# ReuseBlock_1_2024-11-17.net
KiCad netlist of a schematic drawn in EasyEDA Pro
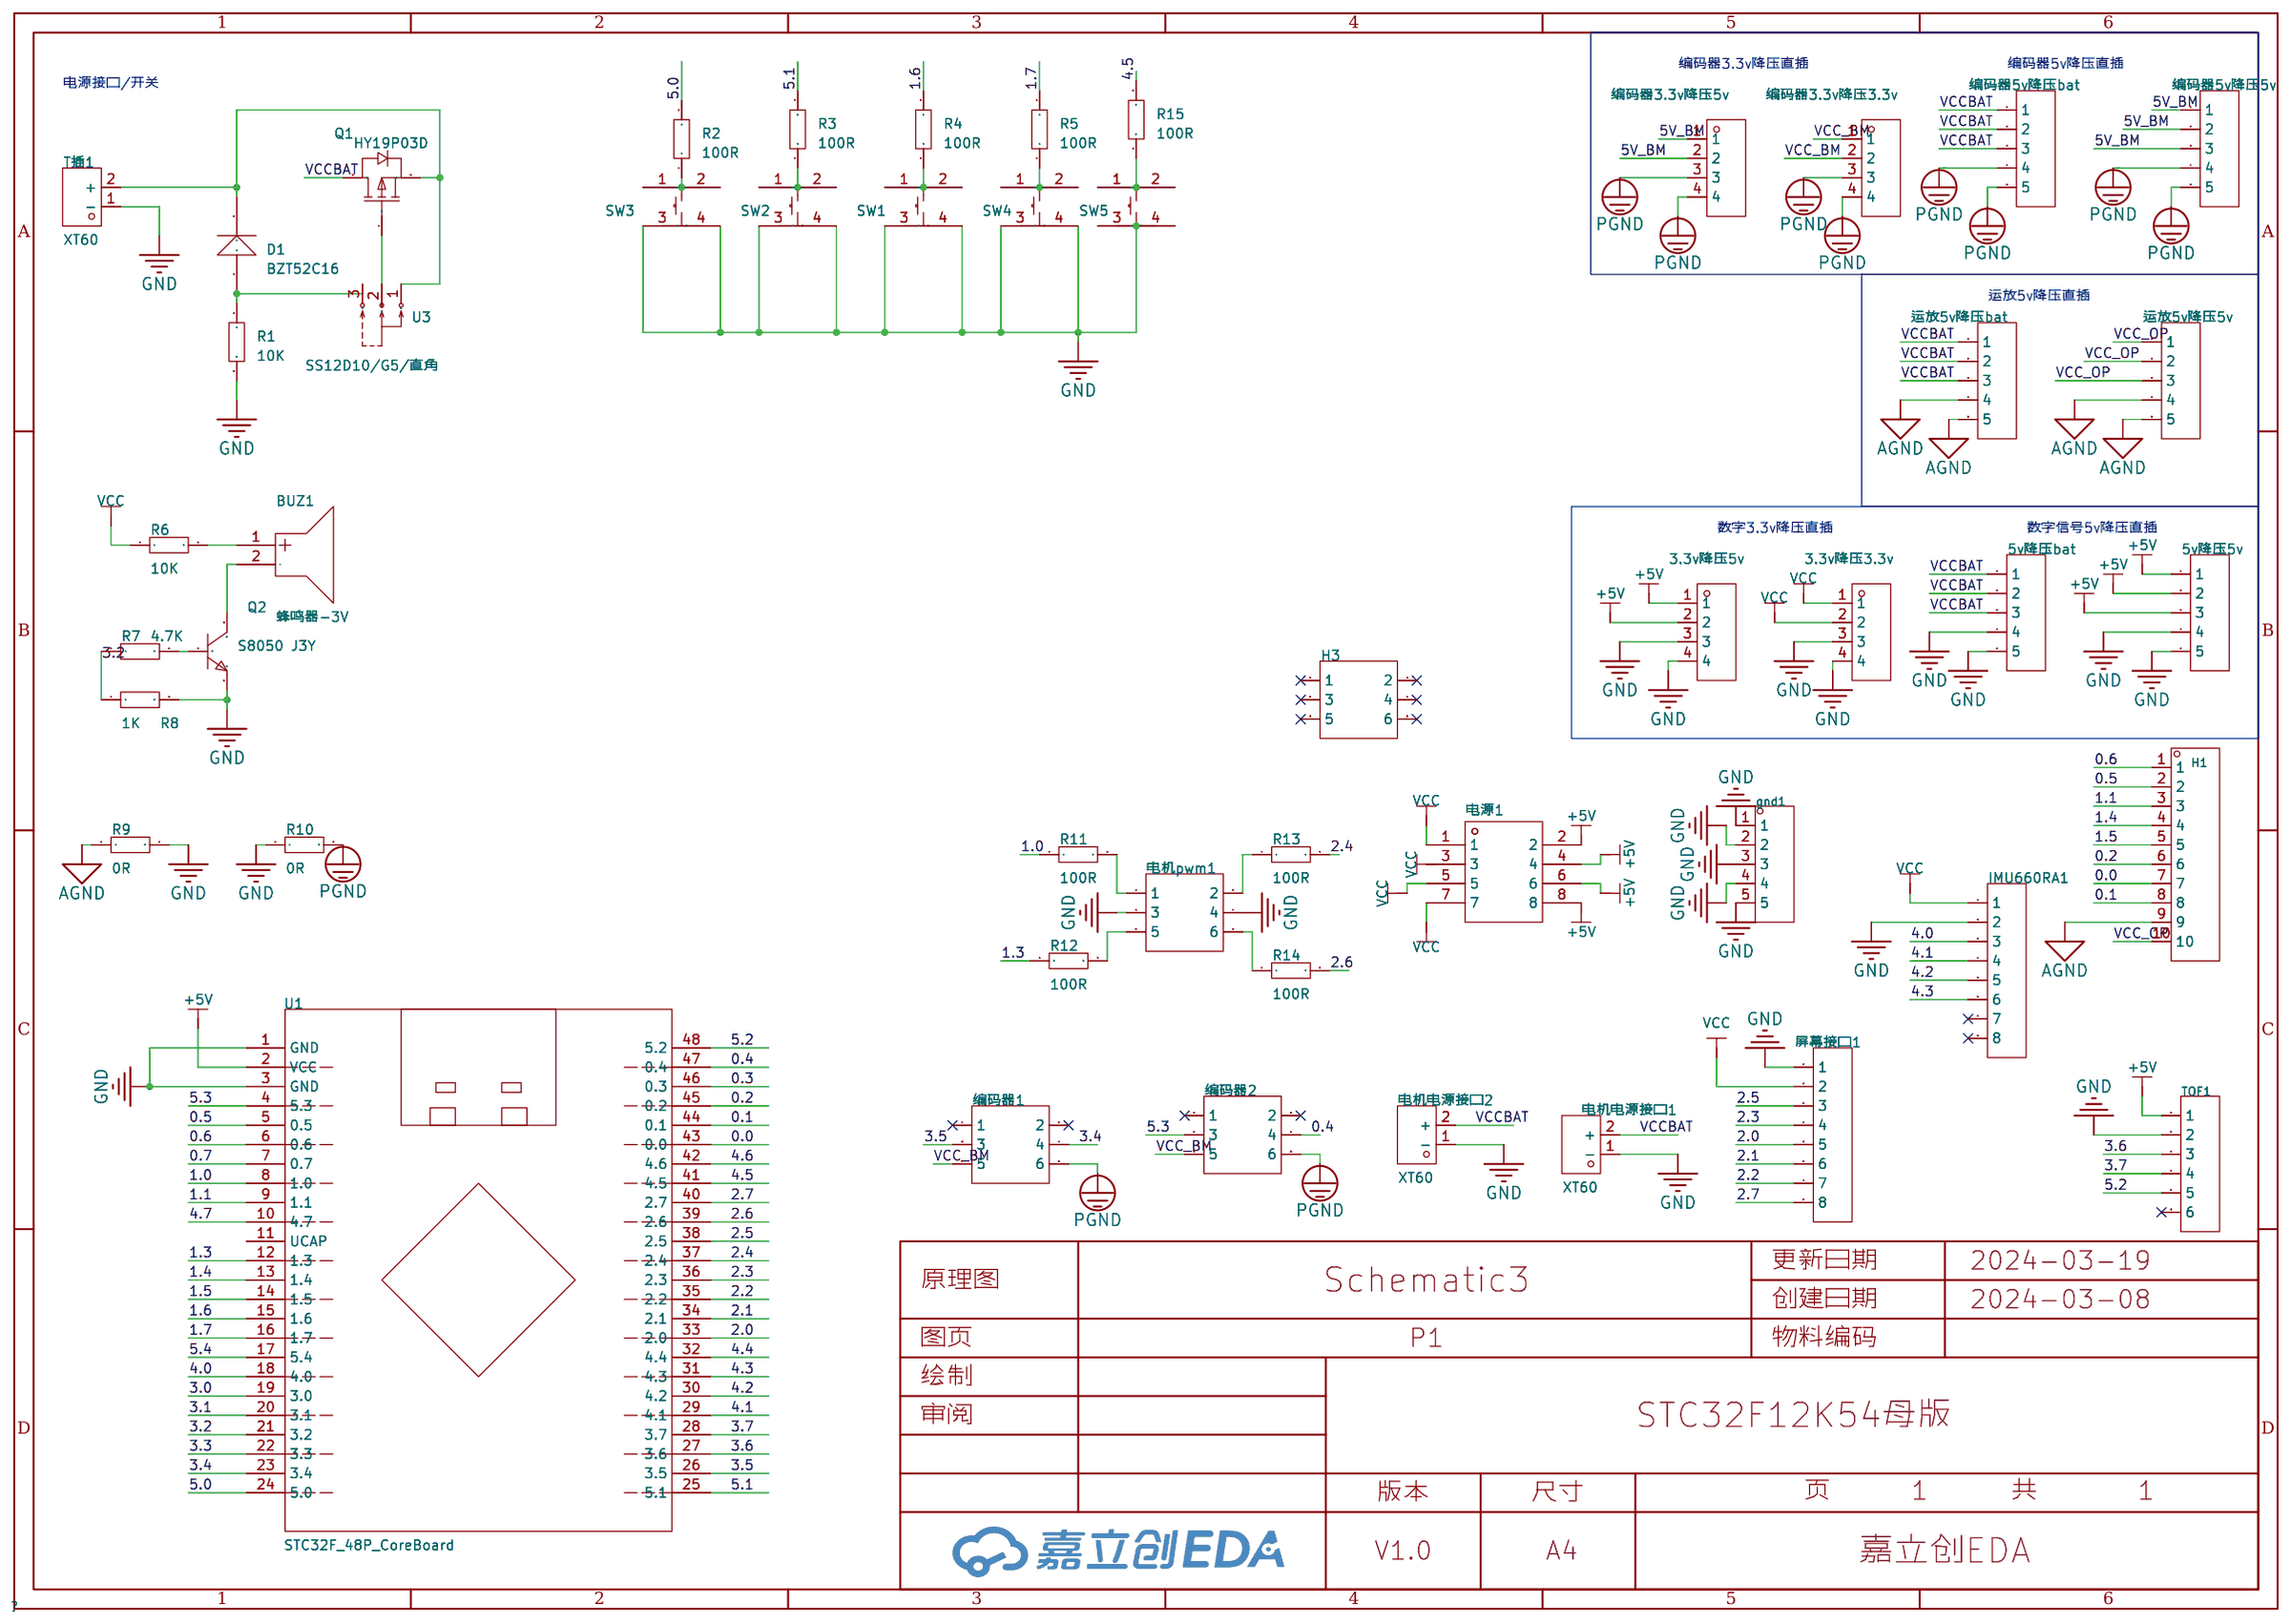
[diagram p0: schematic sheet]

(export (version "E")
  (design (tool "Eeschema 10.0.6"))
  (components
    (comp (ref "3.3v降压3.3v")
      (value "~")
      (footprint "easyedapro:HDR-TH_4P-P2.54-V-F")
      (libsource (lib "easyedapro") (part "2.54-1*4P母"))
    )
    (comp (ref "3.3v降压5v")
      (value "~")
      (footprint "easyedapro:HDR-TH_4P-P2.54-V-F")
      (libsource (lib "easyedapro") (part "2.54-1*4P母"))
    )
    (comp (ref "5v降压5v")
      (value "~")
      (footprint "easyedapro:HDR-TH_5P-P2.54-V-F")
      (libsource (lib "easyedapro") (part "Header-Female-2.54_1x5"))
    )
    (comp (ref "5v降压bat")
      (value "~")
      (footprint "easyedapro:HDR-TH_5P-P2.54-V-F")
      (libsource (lib "easyedapro") (part "Header-Female-2.54_1x5"))
    )
    (comp (ref "BUZ1")
      (value "蜂鸣器-3V")
      (footprint "easyedapro:BUZ-TH_BD12.0-P7.60-D0.6-FD")
      (libsource (lib "easyedapro") (part "蜂鸣器-3V"))
    )
    (comp (ref "D1")
      (value "BZT52C16")
      (footprint "easyedapro:SS14")
      (libsource (lib "easyedapro") (part "BZT52C16"))
    )
    (comp (ref "gnd1")
      (value "~")
      (footprint "easyedapro:HDR-TH_5P-P2.54-V-M")
      (libsource (lib "easyedapro") (part "MTP125-1105S1"))
    )
    (comp (ref "H1")
      (value "~")
      (footprint "easyedapro:HDR-TH_10P-P2.54-V-M-1")
      (libsource (lib "easyedapro") (part "Header-Male-2.54_1x10"))
    )
    (comp (ref "H3")
      (value "~")
      (footprint "easyedapro:HDR-TH_6P-P2.54-V-R2-C3-S2.54_A2541WV-2X3P")
      (libsource (lib "easyedapro") (part "HDR-M-2.54_2x3"))
    )
    (comp (ref "IMU660RA1")
      (value "~")
      (footprint "easyedapro:HDR-TH_8P-P2.54-V-F-1")
      (libsource (lib "easyedapro") (part "Header-Female-2.54_1x8"))
    )
    (comp (ref "Q1")
      (value "HY19P03D")
      (footprint "easyedapro:TO-252-3_L6.5-W5.8-P4.58-BL")
      (libsource (lib "easyedapro") (part "HY19P03D_C330375"))
    )
    (comp (ref "Q2")
      (value "S8050 J3Y")
      (footprint "easyedapro:SOT-23-3_L3.0-W1.7-P0.95-LS2.9-BR")
      (description "晶体管类型:NPN;集电极电流(Ic):500mA;集射极击穿电压(Vceo):25V;功率(Pd):300mW;直流电流增益(hFE@Ic,Vce):200@50mA,1V;")
      (fields (field (name "Manufacturer") "CJ(江苏长电/长晶)"))
      (libsource (lib "easyedapro") (part "S8050_C2146"))
    )
    (comp (ref "R1") (value "10K") (footprint "easyedapro:R0603") (libsource (lib "easyedapro") (part "电阻")))
    (comp (ref "R2") (value "100R") (footprint "easyedapro:R0603") (libsource (lib "easyedapro") (part "电阻")))
    (comp (ref "R3") (value "100R") (footprint "easyedapro:R0603") (libsource (lib "easyedapro") (part "电阻")))
    (comp (ref "R4") (value "100R") (footprint "easyedapro:R0603") (libsource (lib "easyedapro") (part "电阻")))
    (comp (ref "R5") (value "100R") (footprint "easyedapro:R0603") (libsource (lib "easyedapro") (part "电阻")))
    (comp (ref "R6") (value "10K") (footprint "easyedapro:R0603") (libsource (lib "easyedapro") (part "电阻")))
    (comp (ref "R7") (value "4.7K") (footprint "easyedapro:R0603") (libsource (lib "easyedapro") (part "电阻")))
    (comp (ref "R8") (value "1K") (footprint "easyedapro:R0603") (libsource (lib "easyedapro") (part "电阻")))
    (comp (ref "R9") (value "0R") (footprint "easyedapro:R0603") (libsource (lib "easyedapro") (part "电阻")))
    (comp (ref "R10") (value "0R") (footprint "easyedapro:R0603") (libsource (lib "easyedapro") (part "电阻")))
    (comp (ref "R11")
      (value "100R")
      (footprint "easyedapro:R0603")
      (libsource (lib "easyedapro") (part "电阻"))
    )
    (comp (ref "R12")
      (value "100R")
      (footprint "easyedapro:R0603")
      (libsource (lib "easyedapro") (part "电阻"))
    )
    (comp (ref "R13")
      (value "100R")
      (footprint "easyedapro:R0603")
      (libsource (lib "easyedapro") (part "电阻"))
    )
    (comp (ref "R14")
      (value "100R")
      (footprint "easyedapro:R0603")
      (libsource (lib "easyedapro") (part "电阻"))
    )
    (comp (ref "R15")
      (value "100R")
      (footprint "easyedapro:R0603")
      (libsource (lib "easyedapro") (part "电阻"))
    )
    (comp (ref "SW1")
      (value "TS-1095S-A2B3-C2D1")
      (footprint "easyedapro:SW-SMD_4P-L6.0-W6.0-P4.50-LS8.5")
      (description "电路结构:单刀单掷;按钮形状:圆形按钮;安装方式:-;开关长度:6mm;开关宽度:6mm;开关高度:4.5mm;带灯:-;机械寿命:-;")
      (fields (field (name "Manufacturer") "Yuandi(元迪)"))
      (libsource (lib "easyedapro") (part "TS-1095S-A2B3-C2D1"))
    )
    (comp (ref "SW2")
      (value "TS-1095S-A2B3-C2D1")
      (footprint "easyedapro:SW-SMD_4P-L6.0-W6.0-P4.50-LS8.5")
      (description "电路结构:单刀单掷;按钮形状:圆形按钮;安装方式:-;开关长度:6mm;开关宽度:6mm;开关高度:4.5mm;带灯:-;机械寿命:-;")
      (fields (field (name "Manufacturer") "Yuandi(元迪)"))
      (libsource (lib "easyedapro") (part "TS-1095S-A2B3-C2D1"))
    )
    (comp (ref "SW3")
      (value "TS-1095S-A2B3-C2D1")
      (footprint "easyedapro:SW-SMD_4P-L6.0-W6.0-P4.50-LS8.5")
      (description "电路结构:单刀单掷;按钮形状:圆形按钮;安装方式:-;开关长度:6mm;开关宽度:6mm;开关高度:4.5mm;带灯:-;机械寿命:-;")
      (fields (field (name "Manufacturer") "Yuandi(元迪)"))
      (libsource (lib "easyedapro") (part "TS-1095S-A2B3-C2D1"))
    )
    (comp (ref "SW4")
      (value "TS-1095S-A2B3-C2D1")
      (footprint "easyedapro:SW-SMD_4P-L6.0-W6.0-P4.50-LS8.5")
      (description "电路结构:单刀单掷;按钮形状:圆形按钮;安装方式:-;开关长度:6mm;开关宽度:6mm;开关高度:4.5mm;带灯:-;机械寿命:-;")
      (fields (field (name "Manufacturer") "Yuandi(元迪)"))
      (libsource (lib "easyedapro") (part "TS-1095S-A2B3-C2D1"))
    )
    (comp (ref "SW5")
      (value "TS-1095S-A2B3-C2D1")
      (footprint "easyedapro:SW-SMD_4P-L6.0-W6.0-P4.50-LS8.5")
      (description "电路结构:单刀单掷;按钮形状:圆形按钮;安装方式:-;开关长度:6mm;开关宽度:6mm;开关高度:4.5mm;带灯:-;机械寿命:-;")
      (fields (field (name "Manufacturer") "Yuandi(元迪)"))
      (libsource (lib "easyedapro") (part "TS-1095S-A2B3-C2D1"))
    )
    (comp (ref "TOF1")
      (value "~")
      (footprint "easyedapro:HDR-TH_6P-P2.54-V-M-1")
      (libsource (lib "easyedapro") (part "Header-Male-2.54_1x6"))
    )
    (comp (ref "T插1")
      (value "XT60")
      (footprint "easyedapro:CONN-TH_XT60")
      (fields (field (name "Manufacturer") "AMASS(艾迈斯)"))
      (libsource (lib "easyedapro") (part "XT60"))
    )
    (comp (ref "U1")
      (value "STC32F_48P_CoreBoard")
      (footprint "easyedapro:STC32F_48P")
      (description "逐飞科技STC32F核心板")
      (libsource (lib "easyedapro") (part "STC32F_48P_CoreBoard"))
    )
    (comp (ref "U3")
      (value "SS12D10/G5/直角")
      (footprint "easyedapro:SW-TH_SHOU-HAN_SS12D10G4")
      (libsource (lib "easyedapro") (part "SS12D10/G5/直角"))
    )
    (comp (ref "屏幕接口1")
      (value "~")
      (footprint "easyedapro:HDR-TH_8P-P2.54-V-F-1")
      (libsource (lib "easyedapro") (part "Header-Female-2.54_1x8"))
    )
    (comp (ref "电机pwm1")
      (value "~")
      (footprint "easyedapro:HDR-TH_6P-P2.54-V-R2-C3-S2.54_A2541WV-2X3P")
      (libsource (lib "easyedapro") (part "HDR-M-2.54_2x3"))
    )
    (comp (ref "电机电源接口1")
      (value "XT60")
      (footprint "easyedapro:CONN-TH_XT60")
      (fields (field (name "Manufacturer") "AMASS(艾迈斯)"))
      (libsource (lib "easyedapro") (part "XT60"))
    )
    (comp (ref "电机电源接口2")
      (value "XT60")
      (footprint "easyedapro:CONN-TH_XT60")
      (fields (field (name "Manufacturer") "AMASS(艾迈斯)"))
      (libsource (lib "easyedapro") (part "XT60"))
    )
    (comp (ref "电源1")
      (value "~")
      (footprint "easyedapro:HDR-TH_8P-P2.54-V-M-R2-C4-S2.54")
      (libsource (lib "easyedapro") (part "HDR-M-2.54_2x4"))
    )
    (comp (ref "编码器1")
      (value "~")
      (footprint "easyedapro:HDR-TH_6P-P2.54-V-R2-C3-S2.54_A2541WV-2X3P")
      (libsource (lib "easyedapro") (part "HDR-M-2.54_2x3"))
    )
    (comp (ref "编码器2")
      (value "~")
      (footprint "easyedapro:HDR-TH_6P-P2.54-V-R2-C3-S2.54_A2541WV-2X3P")
      (libsource (lib "easyedapro") (part "HDR-M-2.54_2x3"))
    )
    (comp (ref "编码器3.3v降压3.3v")
      (value "~")
      (footprint "easyedapro:HDR-TH_4P-P2.54-V-F")
      (libsource (lib "easyedapro") (part "2.54-1*4P母"))
    )
    (comp (ref "编码器3.3v降压5v")
      (value "~")
      (footprint "easyedapro:HDR-TH_4P-P2.54-V-F")
      (libsource (lib "easyedapro") (part "2.54-1*4P母"))
    )
    (comp (ref "编码器5v降压5v")
      (value "~")
      (footprint "easyedapro:HDR-TH_5P-P2.54-V-F")
      (libsource (lib "easyedapro") (part "Header-Female-2.54_1x5"))
    )
    (comp (ref "编码器5v降压bat")
      (value "~")
      (footprint "easyedapro:HDR-TH_5P-P2.54-V-F")
      (libsource (lib "easyedapro") (part "Header-Female-2.54_1x5"))
    )
    (comp (ref "运放5v降压5v")
      (value "~")
      (footprint "easyedapro:HDR-TH_5P-P2.54-V-F")
      (libsource (lib "easyedapro") (part "Header-Female-2.54_1x5"))
    )
    (comp (ref "运放5v降压bat")
      (value "~")
      (footprint "easyedapro:HDR-TH_5P-P2.54-V-F")
      (libsource (lib "easyedapro") (part "Header-Female-2.54_1x5"))
    )
  )
  (nets
    (net (code "1") (name "+5V") (class "Default")
      (node (ref "3.3v降压5v") (pin "1") (pinfunction "1_1") (pintype "unspecified"))
      (node (ref "3.3v降压5v") (pin "2") (pinfunction "2_2") (pintype "unspecified"))
      (node (ref "5v降压5v") (pin "1") (pinfunction "1_1") (pintype "input"))
      (node (ref "5v降压5v") (pin "2") (pinfunction "2_2") (pintype "input"))
      (node (ref "5v降压5v") (pin "3") (pinfunction "3_3") (pintype "input"))
      (node (ref "TOF1") (pin "1") (pinfunction "1_1") (pintype "input"))
      (node (ref "U1") (pin "2") (pinfunction "VCC_2") (pintype "unspecified"))
      (node (ref "电源1") (pin "2") (pinfunction "2_2") (pintype "input"))
      (node (ref "电源1") (pin "4") (pinfunction "4_4") (pintype "input"))
      (node (ref "电源1") (pin "6") (pinfunction "6_6") (pintype "input"))
      (node (ref "电源1") (pin "8") (pinfunction "8_8") (pintype "input"))
    )
    (net (code "2") (name "/0.0") (class "Default")
      (node (ref "H1") (pin "7") (pinfunction "7_7") (pintype "input"))
      (node (ref "U1") (pin "43") (pinfunction "0.0_43") (pintype "unspecified"))
    )
    (net (code "3") (name "/0.1") (class "Default")
      (node (ref "H1") (pin "8") (pinfunction "8_8") (pintype "input"))
      (node (ref "U1") (pin "44") (pinfunction "0.1_44") (pintype "unspecified"))
    )
    (net (code "4") (name "/0.2") (class "Default")
      (node (ref "H1") (pin "6") (pinfunction "6_6") (pintype "input"))
      (node (ref "U1") (pin "45") (pinfunction "0.2_45") (pintype "unspecified"))
    )
    (net (code "5") (name "/0.3") (class "Default")
      (node (ref "U1") (pin "46") (pinfunction "0.3_46") (pintype "unspecified"))
    )
    (net (code "6") (name "/0.4") (class "Default")
      (node (ref "U1") (pin "47") (pinfunction "0.4_47") (pintype "unspecified"))
      (node (ref "编码器2") (pin "4") (pinfunction "4_4") (pintype "input"))
    )
    (net (code "7") (name "/0.5") (class "Default")
      (node (ref "H1") (pin "2") (pinfunction "2_2") (pintype "input"))
      (node (ref "U1") (pin "5") (pinfunction "0.5_5") (pintype "unspecified"))
    )
    (net (code "8") (name "/0.6") (class "Default")
      (node (ref "H1") (pin "1") (pinfunction "1_1") (pintype "input"))
      (node (ref "U1") (pin "6") (pinfunction "0.6_6") (pintype "unspecified"))
    )
    (net (code "9") (name "/0.7") (class "Default")
      (node (ref "U1") (pin "7") (pinfunction "0.7_7") (pintype "unspecified"))
    )
    (net (code "10") (name "/1.0") (class "Default")
      (node (ref "R11") (pin "1") (pinfunction "1_1") (pintype "input"))
      (node (ref "U1") (pin "8") (pinfunction "1.0_8") (pintype "unspecified"))
    )
    (net (code "11") (name "/1.1") (class "Default")
      (node (ref "H1") (pin "3") (pinfunction "3_3") (pintype "input"))
      (node (ref "U1") (pin "9") (pinfunction "1.1_9") (pintype "unspecified"))
    )
    (net (code "12") (name "/1.3") (class "Default")
      (node (ref "R12") (pin "1") (pinfunction "1_1") (pintype "input"))
      (node (ref "U1") (pin "12") (pinfunction "1.3_12") (pintype "unspecified"))
    )
    (net (code "13") (name "/1.4") (class "Default")
      (node (ref "H1") (pin "4") (pinfunction "4_4") (pintype "input"))
      (node (ref "U1") (pin "13") (pinfunction "1.4_13") (pintype "unspecified"))
    )
    (net (code "14") (name "/1.5") (class "Default")
      (node (ref "H1") (pin "5") (pinfunction "5_5") (pintype "input"))
      (node (ref "U1") (pin "14") (pinfunction "1.5_14") (pintype "unspecified"))
    )
    (net (code "15") (name "/1.6") (class "Default")
      (node (ref "R4") (pin "2") (pinfunction "2_2") (pintype "input"))
      (node (ref "U1") (pin "15") (pinfunction "1.6_15") (pintype "unspecified"))
    )
    (net (code "16") (name "/1.7") (class "Default")
      (node (ref "R5") (pin "2") (pinfunction "2_2") (pintype "input"))
      (node (ref "U1") (pin "16") (pinfunction "1.7_16") (pintype "unspecified"))
    )
    (net (code "17") (name "/2.0") (class "Default")
      (node (ref "U1") (pin "33") (pinfunction "2.0_33") (pintype "unspecified"))
      (node (ref "屏幕接口1") (pin "5") (pinfunction "5_5") (pintype "input"))
    )
    (net (code "18") (name "/2.1") (class "Default")
      (node (ref "U1") (pin "34") (pinfunction "2.1_34") (pintype "unspecified"))
      (node (ref "屏幕接口1") (pin "6") (pinfunction "6_6") (pintype "input"))
    )
    (net (code "19") (name "/2.2") (class "Default")
      (node (ref "U1") (pin "35") (pinfunction "2.2_35") (pintype "unspecified"))
      (node (ref "屏幕接口1") (pin "7") (pinfunction "7_7") (pintype "input"))
    )
    (net (code "20") (name "/2.3") (class "Default")
      (node (ref "U1") (pin "36") (pinfunction "2.3_36") (pintype "unspecified"))
      (node (ref "屏幕接口1") (pin "4") (pinfunction "4_4") (pintype "input"))
    )
    (net (code "21") (name "/2.4") (class "Default")
      (node (ref "R13") (pin "2") (pinfunction "2_2") (pintype "input"))
      (node (ref "U1") (pin "37") (pinfunction "2.4_37") (pintype "unspecified"))
    )
    (net (code "22") (name "/2.5") (class "Default")
      (node (ref "U1") (pin "38") (pinfunction "2.5_38") (pintype "unspecified"))
      (node (ref "屏幕接口1") (pin "3") (pinfunction "3_3") (pintype "input"))
    )
    (net (code "23") (name "/2.6") (class "Default")
      (node (ref "R14") (pin "2") (pinfunction "2_2") (pintype "input"))
      (node (ref "U1") (pin "39") (pinfunction "2.6_39") (pintype "unspecified"))
    )
    (net (code "24") (name "/2.7") (class "Default")
      (node (ref "U1") (pin "40") (pinfunction "2.7_40") (pintype "unspecified"))
      (node (ref "屏幕接口1") (pin "8") (pinfunction "8_8") (pintype "input"))
    )
    (net (code "25") (name "/3.0") (class "Default")
      (node (ref "U1") (pin "19") (pinfunction "3.0_19") (pintype "unspecified"))
    )
    (net (code "26") (name "/3.1") (class "Default")
      (node (ref "U1") (pin "20") (pinfunction "3.1_20") (pintype "unspecified"))
    )
    (net (code "27") (name "/3.2") (class "Default")
      (node (ref "R7") (pin "1") (pinfunction "1_1") (pintype "input"))
      (node (ref "R8") (pin "1") (pinfunction "1_1") (pintype "input"))
      (node (ref "U1") (pin "21") (pinfunction "3.2_21") (pintype "unspecified"))
    )
    (net (code "28") (name "/3.3") (class "Default")
      (node (ref "U1") (pin "22") (pinfunction "3.3_22") (pintype "unspecified"))
    )
    (net (code "29") (name "/3.4") (class "Default")
      (node (ref "U1") (pin "23") (pinfunction "3.4_23") (pintype "unspecified"))
      (node (ref "编码器1") (pin "4") (pinfunction "4_4") (pintype "input"))
    )
    (net (code "30") (name "/3.5") (class "Default")
      (node (ref "U1") (pin "26") (pinfunction "3.5_26") (pintype "unspecified"))
      (node (ref "编码器1") (pin "3") (pinfunction "3_3") (pintype "input"))
    )
    (net (code "31") (name "/3.6") (class "Default")
      (node (ref "TOF1") (pin "3") (pinfunction "3_3") (pintype "input"))
      (node (ref "U1") (pin "27") (pinfunction "3.6_27") (pintype "unspecified"))
    )
    (net (code "32") (name "/3.7") (class "Default")
      (node (ref "TOF1") (pin "4") (pinfunction "4_4") (pintype "input"))
      (node (ref "U1") (pin "28") (pinfunction "3.7_28") (pintype "unspecified"))
    )
    (net (code "33") (name "/4.0") (class "Default")
      (node (ref "IMU660RA1") (pin "3") (pinfunction "3_3") (pintype "input"))
      (node (ref "U1") (pin "18") (pinfunction "4.0_18") (pintype "unspecified"))
    )
    (net (code "34") (name "/4.1") (class "Default")
      (node (ref "IMU660RA1") (pin "4") (pinfunction "4_4") (pintype "input"))
      (node (ref "U1") (pin "29") (pinfunction "4.1_29") (pintype "unspecified"))
    )
    (net (code "35") (name "/4.2") (class "Default")
      (node (ref "IMU660RA1") (pin "5") (pinfunction "5_5") (pintype "input"))
      (node (ref "U1") (pin "30") (pinfunction "4.2_30") (pintype "unspecified"))
    )
    (net (code "36") (name "/4.3") (class "Default")
      (node (ref "IMU660RA1") (pin "6") (pinfunction "6_6") (pintype "input"))
      (node (ref "U1") (pin "31") (pinfunction "4.3_31") (pintype "unspecified"))
    )
    (net (code "37") (name "/4.4") (class "Default")
      (node (ref "U1") (pin "32") (pinfunction "4.4_32") (pintype "unspecified"))
    )
    (net (code "38") (name "/4.5") (class "Default")
      (node (ref "R15") (pin "2") (pinfunction "2_2") (pintype "input"))
      (node (ref "U1") (pin "41") (pinfunction "4.5_41") (pintype "unspecified"))
    )
    (net (code "39") (name "/4.6") (class "Default")
      (node (ref "U1") (pin "42") (pinfunction "4.6_42") (pintype "unspecified"))
    )
    (net (code "40") (name "/4.7") (class "Default")
      (node (ref "U1") (pin "10") (pinfunction "4.7_10") (pintype "unspecified"))
    )
    (net (code "41") (name "/5.0") (class "Default")
      (node (ref "R2") (pin "2") (pinfunction "2_2") (pintype "input"))
      (node (ref "U1") (pin "24") (pinfunction "5.0_24") (pintype "unspecified"))
    )
    (net (code "42") (name "/5.1") (class "Default")
      (node (ref "R3") (pin "2") (pinfunction "2_2") (pintype "input"))
      (node (ref "U1") (pin "25") (pinfunction "5.1_25") (pintype "unspecified"))
    )
    (net (code "43") (name "/5.2") (class "Default")
      (node (ref "TOF1") (pin "5") (pinfunction "5_5") (pintype "input"))
      (node (ref "U1") (pin "48") (pinfunction "5.2_48") (pintype "unspecified"))
    )
    (net (code "44") (name "/5.3") (class "Default")
      (node (ref "U1") (pin "4") (pinfunction "5.3_4") (pintype "unspecified"))
      (node (ref "编码器2") (pin "3") (pinfunction "3_3") (pintype "input"))
    )
    (net (code "45") (name "/5.4") (class "Default")
      (node (ref "U1") (pin "17") (pinfunction "5.4_17") (pintype "unspecified"))
    )
    (net (code "46") (name "/5V_BM") (class "Default")
      (node (ref "编码器3.3v降压5v") (pin "1") (pinfunction "1_1") (pintype "unspecified"))
      (node (ref "编码器3.3v降压5v") (pin "2") (pinfunction "2_2") (pintype "unspecified"))
      (node (ref "编码器5v降压5v") (pin "1") (pinfunction "1_1") (pintype "input"))
      (node (ref "编码器5v降压5v") (pin "2") (pinfunction "2_2") (pintype "input"))
      (node (ref "编码器5v降压5v") (pin "3") (pinfunction "3_3") (pintype "input"))
    )
    (net (code "47") (name "/VCCBAT") (class "Default")
      (node (ref "5v降压bat") (pin "1") (pinfunction "1_1") (pintype "input"))
      (node (ref "5v降压bat") (pin "2") (pinfunction "2_2") (pintype "input"))
      (node (ref "5v降压bat") (pin "3") (pinfunction "3_3") (pintype "input"))
      (node (ref "Q1") (pin "2") (pinfunction "D_2") (pintype "unspecified"))
      (node (ref "电机电源接口1") (pin "2") (pinfunction "+_2") (pintype "input"))
      (node (ref "电机电源接口2") (pin "2") (pinfunction "+_2") (pintype "input"))
      (node (ref "编码器5v降压bat") (pin "1") (pinfunction "1_1") (pintype "input"))
      (node (ref "编码器5v降压bat") (pin "2") (pinfunction "2_2") (pintype "input"))
      (node (ref "编码器5v降压bat") (pin "3") (pinfunction "3_3") (pintype "input"))
      (node (ref "运放5v降压bat") (pin "1") (pinfunction "1_1") (pintype "input"))
      (node (ref "运放5v降压bat") (pin "2") (pinfunction "2_2") (pintype "input"))
      (node (ref "运放5v降压bat") (pin "3") (pinfunction "3_3") (pintype "input"))
    )
    (net (code "48") (name "/VCC_BM") (class "Default")
      (node (ref "编码器1") (pin "5") (pinfunction "5_5") (pintype "input"))
      (node (ref "编码器2") (pin "5") (pinfunction "5_5") (pintype "input"))
      (node (ref "编码器3.3v降压3.3v") (pin "1") (pinfunction "1_1") (pintype "unspecified"))
      (node (ref "编码器3.3v降压3.3v") (pin "2") (pinfunction "2_2") (pintype "unspecified"))
    )
    (net (code "49") (name "/VCC_OP") (class "Default")
      (node (ref "H1") (pin "10") (pinfunction "10_10") (pintype "input"))
      (node (ref "运放5v降压5v") (pin "1") (pinfunction "1_1") (pintype "input"))
      (node (ref "运放5v降压5v") (pin "2") (pinfunction "2_2") (pintype "input"))
      (node (ref "运放5v降压5v") (pin "3") (pinfunction "3_3") (pintype "input"))
    )
    (net (code "50") (name "AGND") (class "Default")
      (node (ref "H1") (pin "9") (pinfunction "9_9") (pintype "input"))
      (node (ref "R9") (pin "1") (pinfunction "1_1") (pintype "input"))
      (node (ref "运放5v降压5v") (pin "4") (pinfunction "4_4") (pintype "input"))
      (node (ref "运放5v降压5v") (pin "5") (pinfunction "5_5") (pintype "input"))
      (node (ref "运放5v降压bat") (pin "4") (pinfunction "4_4") (pintype "input"))
      (node (ref "运放5v降压bat") (pin "5") (pinfunction "5_5") (pintype "input"))
    )
    (net (code "51") (name "GND") (class "Default")
      (node (ref "3.3v降压3.3v") (pin "3") (pinfunction "3_3") (pintype "unspecified"))
      (node (ref "3.3v降压3.3v") (pin "4") (pinfunction "4_4") (pintype "unspecified"))
      (node (ref "3.3v降压5v") (pin "3") (pinfunction "3_3") (pintype "unspecified"))
      (node (ref "3.3v降压5v") (pin "4") (pinfunction "4_4") (pintype "unspecified"))
      (node (ref "5v降压5v") (pin "4") (pinfunction "4_4") (pintype "input"))
      (node (ref "5v降压5v") (pin "5") (pinfunction "5_5") (pintype "input"))
      (node (ref "5v降压bat") (pin "4") (pinfunction "4_4") (pintype "input"))
      (node (ref "5v降压bat") (pin "5") (pinfunction "5_5") (pintype "input"))
      (node (ref "IMU660RA1") (pin "2") (pinfunction "2_2") (pintype "input"))
      (node (ref "Q2") (pin "2") (pinfunction "E_2") (pintype "unspecified"))
      (node (ref "R1") (pin "2") (pinfunction "2_2") (pintype "input"))
      (node (ref "R10") (pin "1") (pinfunction "1_1") (pintype "input"))
      (node (ref "R8") (pin "2") (pinfunction "2_2") (pintype "input"))
      (node (ref "R9") (pin "2") (pinfunction "2_2") (pintype "input"))
      (node (ref "SW1") (pin "3") (pinfunction "3_3") (pintype "unspecified"))
      (node (ref "SW1") (pin "4") (pinfunction "4_4") (pintype "unspecified"))
      (node (ref "SW2") (pin "3") (pinfunction "3_3") (pintype "unspecified"))
      (node (ref "SW2") (pin "4") (pinfunction "4_4") (pintype "unspecified"))
      (node (ref "SW3") (pin "3") (pinfunction "3_3") (pintype "unspecified"))
      (node (ref "SW3") (pin "4") (pinfunction "4_4") (pintype "unspecified"))
      (node (ref "SW4") (pin "3") (pinfunction "3_3") (pintype "unspecified"))
      (node (ref "SW4") (pin "4") (pinfunction "4_4") (pintype "unspecified"))
      (node (ref "SW5") (pin "3") (pinfunction "3_3") (pintype "unspecified"))
      (node (ref "SW5") (pin "4") (pinfunction "4_4") (pintype "unspecified"))
      (node (ref "TOF1") (pin "2") (pinfunction "2_2") (pintype "input"))
      (node (ref "T插1") (pin "1") (pinfunction "-_1") (pintype "input"))
      (node (ref "U1") (pin "1") (pinfunction "GND_1") (pintype "unspecified"))
      (node (ref "U1") (pin "3") (pinfunction "GND_3") (pintype "unspecified"))
      (node (ref "gnd1") (pin "1") (pinfunction "1_1") (pintype "input"))
      (node (ref "gnd1") (pin "2") (pinfunction "2_2") (pintype "input"))
      (node (ref "gnd1") (pin "3") (pinfunction "3_3") (pintype "input"))
      (node (ref "gnd1") (pin "4") (pinfunction "4_4") (pintype "input"))
      (node (ref "gnd1") (pin "5") (pinfunction "5_5") (pintype "input"))
      (node (ref "屏幕接口1") (pin "1") (pinfunction "1_1") (pintype "input"))
      (node (ref "电机pwm1") (pin "3") (pinfunction "3_3") (pintype "input"))
      (node (ref "电机pwm1") (pin "4") (pinfunction "4_4") (pintype "input"))
      (node (ref "电机电源接口1") (pin "1") (pinfunction "-_1") (pintype "input"))
      (node (ref "电机电源接口2") (pin "1") (pinfunction "-_1") (pintype "input"))
    )
    (net (code "52") (name "Net-(BUZ1-+)") (class "Default")
      (node (ref "BUZ1") (pin "1") (pinfunction "+_1") (pintype "input"))
      (node (ref "R6") (pin "2") (pinfunction "2_2") (pintype "input"))
    )
    (net (code "53") (name "Net-(BUZ1--)") (class "Default")
      (node (ref "BUZ1") (pin "2") (pinfunction "-_2") (pintype "input"))
      (node (ref "Q2") (pin "3") (pinfunction "C_3") (pintype "unspecified"))
    )
    (net (code "54") (name "Net-(D1-A)") (class "Default")
      (node (ref "D1") (pin "1") (pinfunction "A_1") (pintype "input"))
      (node (ref "R1") (pin "1") (pinfunction "1_1") (pintype "input"))
      (node (ref "U3") (pin "3") (pinfunction "3_3") (pintype "unspecified"))
    )
    (net (code "55") (name "Net-(D1-K)") (class "Default")
      (node (ref "D1") (pin "2") (pinfunction "K_2") (pintype "input"))
      (node (ref "Q1") (pin "3") (pinfunction "S_3") (pintype "unspecified"))
      (node (ref "T插1") (pin "2") (pinfunction "+_2") (pintype "input"))
      (node (ref "U3") (pin "1") (pinfunction "1_1") (pintype "unspecified"))
    )
    (net (code "56") (name "Net-(Q1-G)") (class "Default")
      (node (ref "Q1") (pin "1") (pinfunction "G_1") (pintype "unspecified"))
      (node (ref "U3") (pin "2") (pinfunction "2_2") (pintype "unspecified"))
    )
    (net (code "57") (name "Net-(Q2-B)") (class "Default")
      (node (ref "Q2") (pin "1") (pinfunction "B_1") (pintype "unspecified"))
      (node (ref "R7") (pin "2") (pinfunction "2_2") (pintype "input"))
    )
    (net (code "58") (name "Net-(R2-Pad1)") (class "Default")
      (node (ref "R2") (pin "1") (pinfunction "1_1") (pintype "input"))
      (node (ref "SW3") (pin "1") (pinfunction "1_1") (pintype "unspecified"))
      (node (ref "SW3") (pin "2") (pinfunction "2_2") (pintype "unspecified"))
    )
    (net (code "59") (name "Net-(R3-Pad1)") (class "Default")
      (node (ref "R3") (pin "1") (pinfunction "1_1") (pintype "input"))
      (node (ref "SW2") (pin "1") (pinfunction "1_1") (pintype "unspecified"))
      (node (ref "SW2") (pin "2") (pinfunction "2_2") (pintype "unspecified"))
    )
    (net (code "60") (name "Net-(R4-Pad1)") (class "Default")
      (node (ref "R4") (pin "1") (pinfunction "1_1") (pintype "input"))
      (node (ref "SW1") (pin "1") (pinfunction "1_1") (pintype "unspecified"))
      (node (ref "SW1") (pin "2") (pinfunction "2_2") (pintype "unspecified"))
    )
    (net (code "61") (name "Net-(R5-Pad1)") (class "Default")
      (node (ref "R5") (pin "1") (pinfunction "1_1") (pintype "input"))
      (node (ref "SW4") (pin "1") (pinfunction "1_1") (pintype "unspecified"))
      (node (ref "SW4") (pin "2") (pinfunction "2_2") (pintype "unspecified"))
    )
    (net (code "62") (name "Net-(R11-Pad2)") (class "Default")
      (node (ref "R11") (pin "2") (pinfunction "2_2") (pintype "input"))
      (node (ref "电机pwm1") (pin "1") (pinfunction "1_1") (pintype "input"))
    )
    (net (code "63") (name "Net-(R12-Pad2)") (class "Default")
      (node (ref "R12") (pin "2") (pinfunction "2_2") (pintype "input"))
      (node (ref "电机pwm1") (pin "5") (pinfunction "5_5") (pintype "input"))
    )
    (net (code "64") (name "Net-(R13-Pad1)") (class "Default")
      (node (ref "R13") (pin "1") (pinfunction "1_1") (pintype "input"))
      (node (ref "电机pwm1") (pin "2") (pinfunction "2_2") (pintype "input"))
    )
    (net (code "65") (name "Net-(R14-Pad1)") (class "Default")
      (node (ref "R14") (pin "1") (pinfunction "1_1") (pintype "input"))
      (node (ref "电机pwm1") (pin "6") (pinfunction "6_6") (pintype "input"))
    )
    (net (code "66") (name "Net-(R15-Pad1)") (class "Default")
      (node (ref "R15") (pin "1") (pinfunction "1_1") (pintype "input"))
      (node (ref "SW5") (pin "1") (pinfunction "1_1") (pintype "unspecified"))
      (node (ref "SW5") (pin "2") (pinfunction "2_2") (pintype "unspecified"))
    )
    (net (code "67") (name "PGND") (class "Default")
      (node (ref "R10") (pin "2") (pinfunction "2_2") (pintype "input"))
      (node (ref "编码器1") (pin "6") (pinfunction "6_6") (pintype "input"))
      (node (ref "编码器2") (pin "6") (pinfunction "6_6") (pintype "input"))
      (node (ref "编码器3.3v降压3.3v") (pin "3") (pinfunction "3_3") (pintype "unspecified"))
      (node (ref "编码器3.3v降压3.3v") (pin "4") (pinfunction "4_4") (pintype "unspecified"))
      (node (ref "编码器3.3v降压5v") (pin "3") (pinfunction "3_3") (pintype "unspecified"))
      (node (ref "编码器3.3v降压5v") (pin "4") (pinfunction "4_4") (pintype "unspecified"))
      (node (ref "编码器5v降压5v") (pin "4") (pinfunction "4_4") (pintype "input"))
      (node (ref "编码器5v降压5v") (pin "5") (pinfunction "5_5") (pintype "input"))
      (node (ref "编码器5v降压bat") (pin "4") (pinfunction "4_4") (pintype "input"))
      (node (ref "编码器5v降压bat") (pin "5") (pinfunction "5_5") (pintype "input"))
    )
    (net (code "68") (name "VCC") (class "Default")
      (node (ref "3.3v降压3.3v") (pin "1") (pinfunction "1_1") (pintype "unspecified"))
      (node (ref "3.3v降压3.3v") (pin "2") (pinfunction "2_2") (pintype "unspecified"))
      (node (ref "IMU660RA1") (pin "1") (pinfunction "1_1") (pintype "input"))
      (node (ref "R6") (pin "1") (pinfunction "1_1") (pintype "input"))
      (node (ref "屏幕接口1") (pin "2") (pinfunction "2_2") (pintype "input"))
      (node (ref "电源1") (pin "1") (pinfunction "1_1") (pintype "input"))
      (node (ref "电源1") (pin "3") (pinfunction "3_3") (pintype "input"))
      (node (ref "电源1") (pin "5") (pinfunction "5_5") (pintype "input"))
      (node (ref "电源1") (pin "7") (pinfunction "7_7") (pintype "input"))
    )
    (net (code "69") (name "unconnected-(H3-Pad1)") (class "Default")
      (node (ref "H3") (pin "1") (pinfunction "1_1") (pintype "input+no_connect"))
    )
    (net (code "70") (name "unconnected-(H3-Pad2)") (class "Default")
      (node (ref "H3") (pin "2") (pinfunction "2_2") (pintype "input+no_connect"))
    )
    (net (code "71") (name "unconnected-(H3-Pad3)") (class "Default")
      (node (ref "H3") (pin "3") (pinfunction "3_3") (pintype "input+no_connect"))
    )
    (net (code "72") (name "unconnected-(H3-Pad4)") (class "Default")
      (node (ref "H3") (pin "4") (pinfunction "4_4") (pintype "input+no_connect"))
    )
    (net (code "73") (name "unconnected-(H3-Pad5)") (class "Default")
      (node (ref "H3") (pin "5") (pinfunction "5_5") (pintype "input+no_connect"))
    )
    (net (code "74") (name "unconnected-(H3-Pad6)") (class "Default")
      (node (ref "H3") (pin "6") (pinfunction "6_6") (pintype "input+no_connect"))
    )
    (net (code "75") (name "unconnected-(IMU660RA1-Pad7)") (class "Default")
      (node (ref "IMU660RA1") (pin "7") (pinfunction "7_7") (pintype "input+no_connect"))
    )
    (net (code "76") (name "unconnected-(IMU660RA1-Pad8)") (class "Default")
      (node (ref "IMU660RA1") (pin "8") (pinfunction "8_8") (pintype "input+no_connect"))
    )
    (net (code "77") (name "unconnected-(TOF1-Pad6)") (class "Default")
      (node (ref "TOF1") (pin "6") (pinfunction "6_6") (pintype "input+no_connect"))
    )
    (net (code "78") (name "unconnected-(U1-UCAP-Pad11)") (class "Default")
      (node (ref "U1") (pin "11") (pinfunction "UCAP_11") (pintype "unspecified"))
    )
    (net (code "79") (name "unconnected-(编码器1-Pad1)") (class "Default")
      (node (ref "编码器1") (pin "1") (pinfunction "1_1") (pintype "input+no_connect"))
    )
    (net (code "80") (name "unconnected-(编码器1-Pad2)") (class "Default")
      (node (ref "编码器1") (pin "2") (pinfunction "2_2") (pintype "input+no_connect"))
    )
    (net (code "81") (name "unconnected-(编码器2-Pad1)") (class "Default")
      (node (ref "编码器2") (pin "1") (pinfunction "1_1") (pintype "input+no_connect"))
    )
    (net (code "82") (name "unconnected-(编码器2-Pad2)") (class "Default")
      (node (ref "编码器2") (pin "2") (pinfunction "2_2") (pintype "input+no_connect"))
    )
  )
)
